# STM32F100_Base_Wireless_2.net
KiCad netlist of a schematic drawn in EAGLE
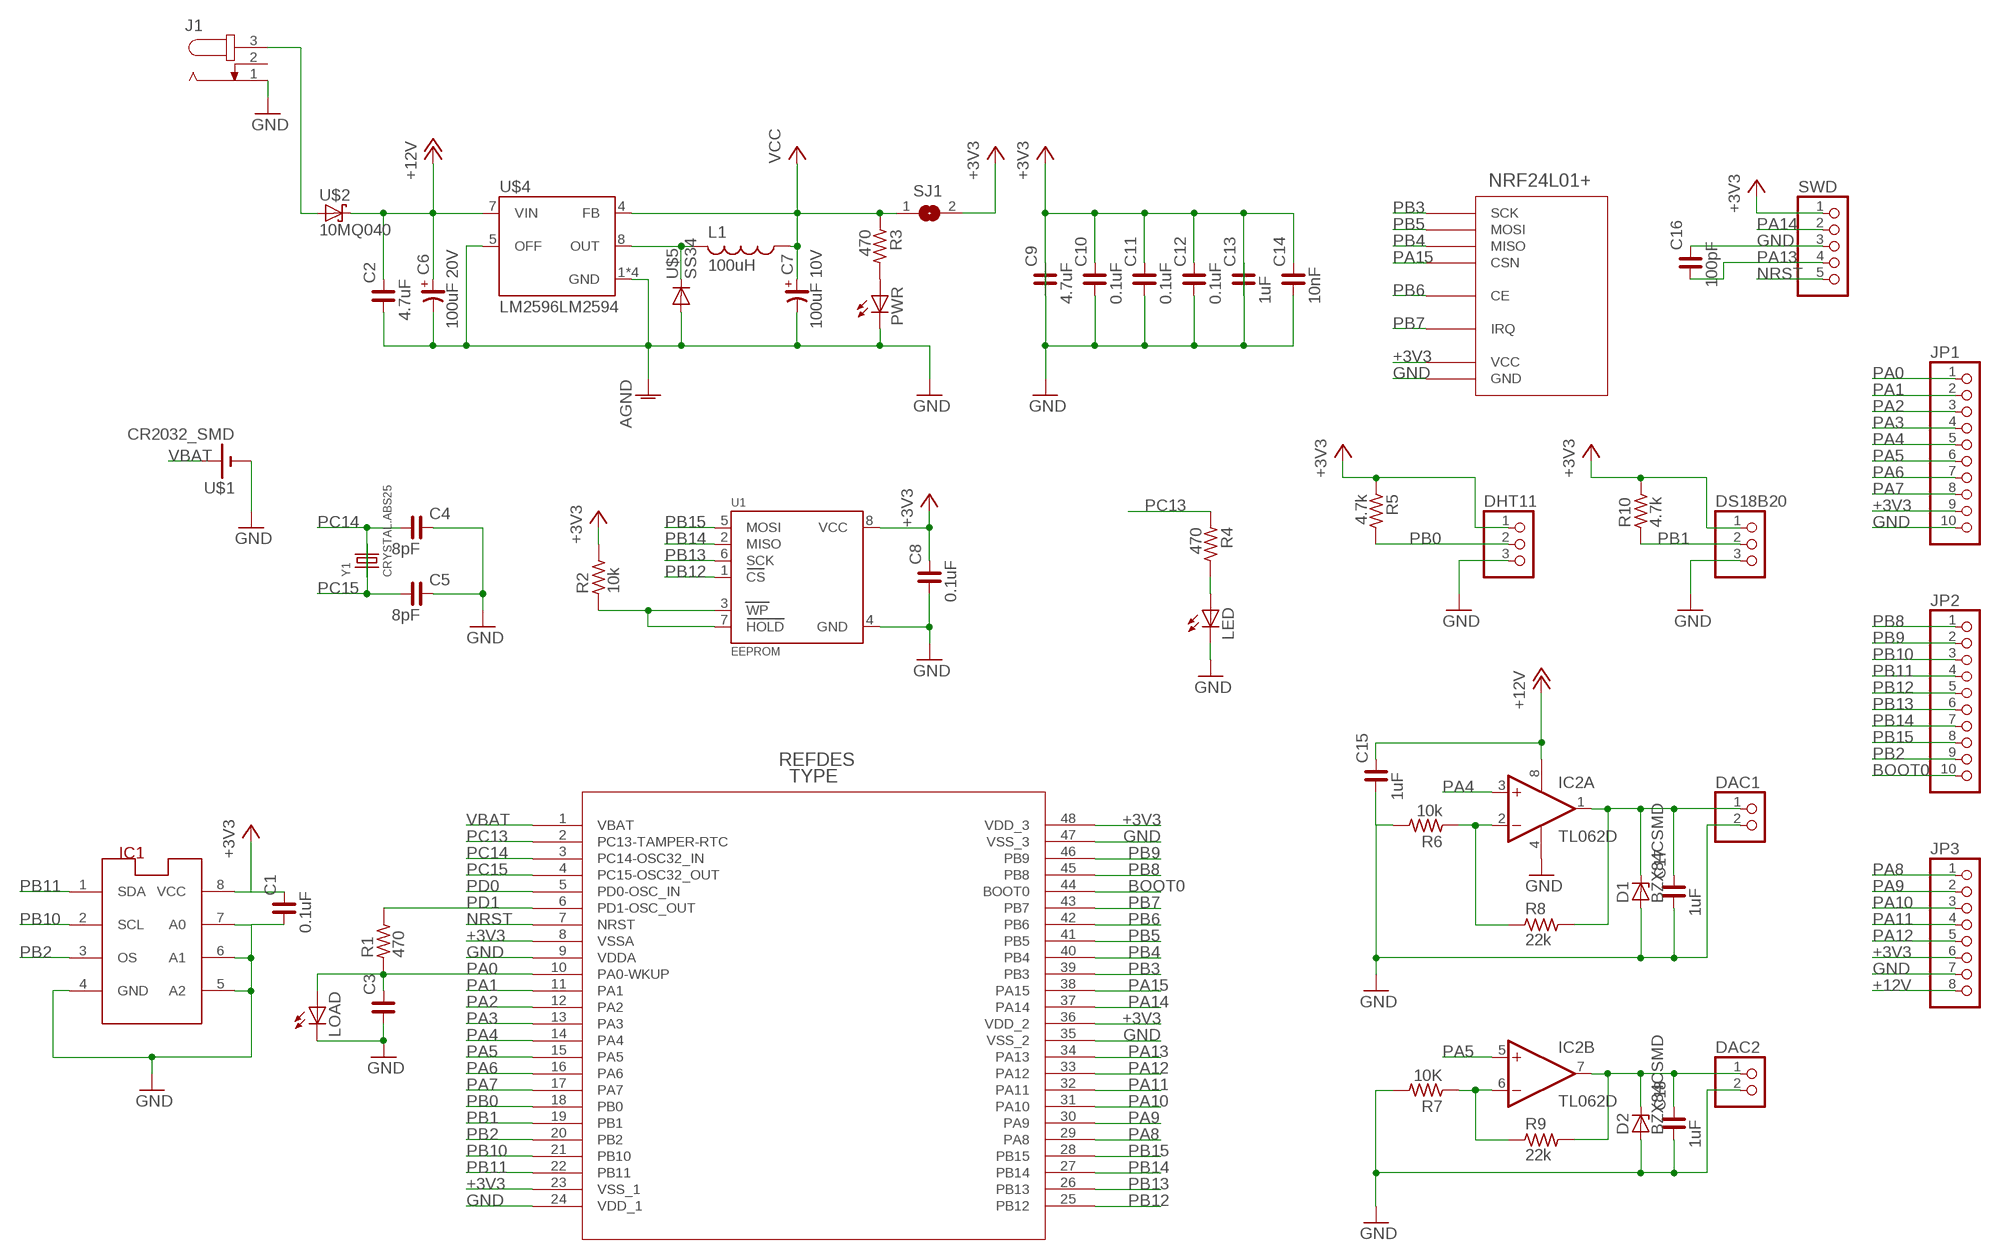
[diagram p0: schematic, sheet 1]

(export (version "E")
  (design (tool "Eeschema 10.0.6"))
  (components
    (comp (ref "C1")
      (value "0.1uF")
      (footprint "eagle-import:C0603")
      (libsource (lib "eagle-import") (part "C_0603"))
    )
    (comp (ref "C2")
      (value "4.7uF")
      (footprint "eagle-import:C0603")
      (libsource (lib "eagle-import") (part "C_0603"))
    )
    (comp (ref "C3")
      (value "C_0603")
      (footprint "eagle-import:C0603")
      (libsource (lib "eagle-import") (part "C_0603"))
    )
    (comp (ref "C4")
      (value "8pF")
      (footprint "eagle-import:C0603")
      (libsource (lib "eagle-import") (part "C_0603"))
    )
    (comp (ref "C5")
      (value "8pF")
      (footprint "eagle-import:C0603")
      (libsource (lib "eagle-import") (part "C_0603"))
    )
    (comp (ref "C6")
      (value "100uF 20V")
      (footprint "eagle-import:C7343_T")
      (libsource (lib "eagle-import") (part "CP_7343"))
    )
    (comp (ref "C7")
      (value "100uF 10V")
      (footprint "eagle-import:C6032-28_T")
      (libsource (lib "eagle-import") (part "CP_6032-28"))
    )
    (comp (ref "C8")
      (value "0.1uF")
      (footprint "eagle-import:C0603")
      (libsource (lib "eagle-import") (part "C_0603"))
    )
    (comp (ref "C9")
      (value "4.7uF")
      (footprint "eagle-import:C0603")
      (libsource (lib "eagle-import") (part "C_0603"))
    )
    (comp (ref "C10")
      (value "0.1uF")
      (footprint "eagle-import:C0603")
      (libsource (lib "eagle-import") (part "C_0603"))
    )
    (comp (ref "C11")
      (value "0.1uF")
      (footprint "eagle-import:C0603")
      (libsource (lib "eagle-import") (part "C_0603"))
    )
    (comp (ref "C12")
      (value "0.1uF")
      (footprint "eagle-import:C0603")
      (libsource (lib "eagle-import") (part "C_0603"))
    )
    (comp (ref "C13")
      (value "1uF")
      (footprint "eagle-import:C0603")
      (libsource (lib "eagle-import") (part "C_0603"))
    )
    (comp (ref "C14")
      (value "10nF")
      (footprint "eagle-import:C0603")
      (libsource (lib "eagle-import") (part "C_0603"))
    )
    (comp (ref "C15")
      (value "1uF")
      (footprint "eagle-import:C0603")
      (libsource (lib "eagle-import") (part "C_0603"))
    )
    (comp (ref "C16")
      (value "100pF")
      (footprint "eagle-import:C0603")
      (libsource (lib "eagle-import") (part "C_0603"))
    )
    (comp (ref "C17")
      (value "1uF")
      (footprint "eagle-import:C0603")
      (libsource (lib "eagle-import") (part "C_0603"))
    )
    (comp (ref "C18")
      (value "1uF")
      (footprint "eagle-import:C0603")
      (libsource (lib "eagle-import") (part "C_0603"))
    )
    (comp (ref "D1")
      (value "BZX84CSMD")
      (footprint "eagle-import:TO236")
      (libsource (lib "eagle-import") (part "BZX84CSMD"))
    )
    (comp (ref "D2")
      (value "BZX84CSMD")
      (footprint "eagle-import:TO236")
      (libsource (lib "eagle-import") (part "BZX84CSMD"))
    )
    (comp (ref "DAC1")
      (value "PINHD-1X02_2.54-S")
      (footprint "eagle-import:1X02-S")
      (libsource (lib "eagle-import") (part "PINHD-1X02_2.54-S"))
    )
    (comp (ref "DAC2")
      (value "PINHD-1X02_2.54-S")
      (footprint "eagle-import:1X02-S")
      (libsource (lib "eagle-import") (part "PINHD-1X02_2.54-S"))
    )
    (comp (ref "DHT11")
      (value "PINHD-1X03_2.54-S")
      (footprint "eagle-import:1X03-S")
      (libsource (lib "eagle-import") (part "PINHD-1X03_2.54-S"))
    )
    (comp (ref "DS18B20")
      (value "PINHD-1X03_2.54-S")
      (footprint "eagle-import:1X03-S")
      (libsource (lib "eagle-import") (part "PINHD-1X03_2.54-S"))
    )
    (comp (ref "IC1")
      (value "LM75_ICN")
      (footprint "eagle-import:SO8_LM75")
      (libsource (lib "eagle-import") (part "LM75_ICN"))
    )
    (comp (ref "IC2")
      (value "TL062D")
      (footprint "eagle-import:SO08")
      (libsource (lib "eagle-import") (part "TL062D"))
    )
    (comp (ref "J1")
      (value "JACK-PLUG0")
      (footprint "eagle-import:SPC4077")
      (libsource (lib "eagle-import") (part "JACK-PLUG0"))
    )
    (comp (ref "JP1")
      (value "PINHD-1X10_2.54-S")
      (footprint "eagle-import:1X10-S")
      (libsource (lib "eagle-import") (part "PINHD-1X10_2.54-S"))
    )
    (comp (ref "JP2")
      (value "PINHD-1X10_2.54-S")
      (footprint "eagle-import:1X10-S")
      (libsource (lib "eagle-import") (part "PINHD-1X10_2.54-S"))
    )
    (comp (ref "JP3")
      (value "PINHD-1X08_2.54-S")
      (footprint "eagle-import:1X08-S")
      (libsource (lib "eagle-import") (part "PINHD-1X08_2.54-S"))
    )
    (comp (ref "L1")
      (value "100uH")
      (footprint "eagle-import:POWER-CHOKE_WE-TPC")
      (libsource (lib "eagle-import") (part "L-USWE-TPC"))
    )
    (comp (ref "LED")
      (value "LEDCHIPLED_1206")
      (footprint "eagle-import:CHIPLED_1206")
      (libsource (lib "eagle-import") (part "LEDCHIPLED_1206"))
    )
    (comp (ref "LOAD")
      (value "LEDCHIPLED_1206")
      (footprint "eagle-import:CHIPLED_1206")
      (libsource (lib "eagle-import") (part "LEDCHIPLED_1206"))
    )
    (comp (ref "PWR")
      (value "LEDCHIPLED_1206")
      (footprint "eagle-import:CHIPLED_1206")
      (libsource (lib "eagle-import") (part "LEDCHIPLED_1206"))
    )
    (comp (ref "R1")
      (value "470")
      (footprint "eagle-import:R1206")
      (libsource (lib "eagle-import") (part "R_1206"))
    )
    (comp (ref "R2")
      (value "10k")
      (footprint "eagle-import:R1206")
      (libsource (lib "eagle-import") (part "R_1206"))
    )
    (comp (ref "R3")
      (value "470")
      (footprint "eagle-import:R1206")
      (libsource (lib "eagle-import") (part "R_1206"))
    )
    (comp (ref "R4")
      (value "470")
      (footprint "eagle-import:R1206")
      (libsource (lib "eagle-import") (part "R_1206"))
    )
    (comp (ref "R5")
      (value "4.7k")
      (footprint "eagle-import:R1206")
      (libsource (lib "eagle-import") (part "R_1206"))
    )
    (comp (ref "R6")
      (value "10k")
      (footprint "eagle-import:R1206")
      (libsource (lib "eagle-import") (part "R_1206"))
    )
    (comp (ref "R7")
      (value "10K")
      (footprint "eagle-import:R1206")
      (libsource (lib "eagle-import") (part "R_1206"))
    )
    (comp (ref "R8")
      (value "22k")
      (footprint "eagle-import:R1206")
      (libsource (lib "eagle-import") (part "R_1206"))
    )
    (comp (ref "R9")
      (value "22k")
      (footprint "eagle-import:R1206")
      (libsource (lib "eagle-import") (part "R_1206"))
    )
    (comp (ref "R10")
      (value "4.7k")
      (footprint "eagle-import:R1206")
      (libsource (lib "eagle-import") (part "R_1206"))
    )
    (comp (ref "SJ1") (value "SJ") (footprint "eagle-import:SJ") (libsource (lib "eagle-import") (part "SJ")))
    (comp (ref "SWD")
      (value "PINHD-1X05_2.54-90°-S")
      (footprint "eagle-import:1X05_90-S")
      (libsource (lib "eagle-import") (part "PINHD-1X05_2.54-90°-S"))
    )
    (comp (ref "U$1")
      (value "CR2032_SMD")
      (footprint "eagle-import:SMD_BH-2")
      (libsource (lib "eagle-import") (part "CR2032_SMD"))
    )
    (comp (ref "U$2")
      (value "10MQ040")
      (footprint "eagle-import:SMA")
      (libsource (lib "eagle-import") (part "10MQ040"))
    )
    (comp (ref "U$3")
      (value "STM32F100C8T6B")
      (footprint "eagle-import:LQFP-48")
      (libsource (lib "eagle-import") (part "STM32F100C8T6B"))
    )
    (comp (ref "U$4")
      (value "LM2596LM2594")
      (footprint "eagle-import:SOIC8_150MIL")
      (libsource (lib "eagle-import") (part "LM2596LM2594"))
    )
    (comp (ref "U$5")
      (value "SS34")
      (footprint "eagle-import:DO214AC")
      (libsource (lib "eagle-import") (part "DIODE-DO214AC"))
    )
    (comp (ref "U$6")
      (value "NRF24L01+")
      (footprint "eagle-import:NRF24L01+")
      (libsource (lib "eagle-import") (part "NRF24L01+"))
    )
    (comp (ref "U1")
      (value "EEPROM")
      (footprint "eagle-import:SOIC8_150MIL")
      (libsource (lib "eagle-import") (part "EEPROM_SPI_AT25040A"))
    )
    (comp (ref "Y1")
      (value "CRYSTAL.ABS25")
      (footprint "eagle-import:ABS25")
      (libsource (lib "eagle-import") (part "CRYSTAL.ABS25"))
    )
  )
  (nets
    (net (code "1") (name "+3V3") (class "Default")
      (node (ref "C1") (pin "2") (pinfunction "2_2") (pintype "passive"))
      (node (ref "C10") (pin "2") (pinfunction "2_2") (pintype "passive"))
      (node (ref "C11") (pin "2") (pinfunction "2_2") (pintype "passive"))
      (node (ref "C12") (pin "2") (pinfunction "2_2") (pintype "passive"))
      (node (ref "C13") (pin "1") (pinfunction "1_1") (pintype "passive"))
      (node (ref "C14") (pin "2") (pinfunction "2_2") (pintype "passive"))
      (node (ref "C8") (pin "2") (pinfunction "2_2") (pintype "passive"))
      (node (ref "C9") (pin "1") (pinfunction "1_1") (pintype "passive"))
      (node (ref "DHT11") (pin "1") (pinfunction "1_1") (pintype "passive"))
      (node (ref "DS18B20") (pin "1") (pinfunction "1_1") (pintype "passive"))
      (node (ref "IC1") (pin "8") (pinfunction "VCC_8") (pintype "power_in"))
      (node (ref "JP1") (pin "9") (pinfunction "9_9") (pintype "passive"))
      (node (ref "JP3") (pin "6") (pinfunction "6_6") (pintype "passive"))
      (node (ref "R10") (pin "2") (pinfunction "2_2") (pintype "passive"))
      (node (ref "R2") (pin "2") (pinfunction "2_2") (pintype "passive"))
      (node (ref "R5") (pin "1") (pinfunction "1_1") (pintype "passive"))
      (node (ref "SJ1") (pin "2") (pinfunction "2_2") (pintype "passive"))
      (node (ref "SWD") (pin "1") (pinfunction "1_1") (pintype "passive"))
      (node (ref "U$3") (pin "23") (pinfunction "VSS_1_23") (pintype "passive"))
      (node (ref "U$3") (pin "36") (pinfunction "VDD_2_36") (pintype "passive"))
      (node (ref "U$3") (pin "48") (pinfunction "VDD_3_48") (pintype "passive"))
      (node (ref "U$3") (pin "8") (pinfunction "VSSA_8") (pintype "passive"))
      (node (ref "U$6") (pin "VCC") (pinfunction "VCC_VCC") (pintype "passive"))
      (node (ref "U1") (pin "8") (pinfunction "VCC_8") (pintype "power_in"))
    )
    (net (code "2") (name "+12V") (class "Default")
      (node (ref "C15") (pin "2") (pinfunction "2_2") (pintype "passive"))
      (node (ref "C2") (pin "2") (pinfunction "2_2") (pintype "passive"))
      (node (ref "C6") (pin "+") (pinfunction "+_+") (pintype "passive"))
      (node (ref "IC2") (pin "8") (pinfunction "V+_8") (pintype "power_in"))
      (node (ref "JP3") (pin "8") (pinfunction "8_8") (pintype "passive"))
      (node (ref "U$2") (pin "C") (pinfunction "C_C") (pintype "passive"))
      (node (ref "U$4") (pin "7") (pinfunction "VIN_7") (pintype "power_in"))
    )
    (net (code "3") (name "/BOOT0") (class "Default")
      (node (ref "JP2") (pin "10") (pinfunction "10_10") (pintype "passive"))
      (node (ref "U$3") (pin "44") (pinfunction "BOOT0_44") (pintype "passive"))
    )
    (net (code "4") (name "/NRST") (class "Default")
      (node (ref "SWD") (pin "5") (pinfunction "5_5") (pintype "passive"))
      (node (ref "U$3") (pin "7") (pinfunction "NRST_7") (pintype "passive"))
    )
    (net (code "5") (name "/PA0") (class "Default")
      (node (ref "C3") (pin "2") (pinfunction "2_2") (pintype "passive"))
      (node (ref "JP1") (pin "1") (pinfunction "1_1") (pintype "passive"))
      (node (ref "LOAD") (pin "A") (pinfunction "A_A") (pintype "passive"))
      (node (ref "R1") (pin "1") (pinfunction "1_1") (pintype "passive"))
      (node (ref "U$3") (pin "10") (pinfunction "PA0-WKUP_10") (pintype "passive"))
    )
    (net (code "6") (name "/PA1") (class "Default")
      (node (ref "JP1") (pin "2") (pinfunction "2_2") (pintype "passive"))
      (node (ref "U$3") (pin "11") (pinfunction "PA1_11") (pintype "passive"))
    )
    (net (code "7") (name "/PA2") (class "Default")
      (node (ref "JP1") (pin "3") (pinfunction "3_3") (pintype "passive"))
      (node (ref "U$3") (pin "12") (pinfunction "PA2_12") (pintype "passive"))
    )
    (net (code "8") (name "/PA3") (class "Default")
      (node (ref "JP1") (pin "4") (pinfunction "4_4") (pintype "passive"))
      (node (ref "U$3") (pin "13") (pinfunction "PA3_13") (pintype "passive"))
    )
    (net (code "9") (name "/PA4") (class "Default")
      (node (ref "IC2") (pin "3") (pinfunction "+IN_3") (pintype "input"))
      (node (ref "JP1") (pin "5") (pinfunction "5_5") (pintype "passive"))
      (node (ref "U$3") (pin "14") (pinfunction "PA4_14") (pintype "passive"))
    )
    (net (code "10") (name "/PA5") (class "Default")
      (node (ref "IC2") (pin "5") (pinfunction "+IN_5") (pintype "input"))
      (node (ref "JP1") (pin "6") (pinfunction "6_6") (pintype "passive"))
      (node (ref "U$3") (pin "15") (pinfunction "PA5_15") (pintype "passive"))
    )
    (net (code "11") (name "/PA6") (class "Default")
      (node (ref "JP1") (pin "7") (pinfunction "7_7") (pintype "passive"))
      (node (ref "U$3") (pin "16") (pinfunction "PA6_16") (pintype "passive"))
    )
    (net (code "12") (name "/PA7") (class "Default")
      (node (ref "JP1") (pin "8") (pinfunction "8_8") (pintype "passive"))
      (node (ref "U$3") (pin "17") (pinfunction "PA7_17") (pintype "passive"))
    )
    (net (code "13") (name "/PA8") (class "Default")
      (node (ref "JP3") (pin "1") (pinfunction "1_1") (pintype "passive"))
      (node (ref "U$3") (pin "29") (pinfunction "PA8_29") (pintype "passive"))
    )
    (net (code "14") (name "/PA9") (class "Default")
      (node (ref "JP3") (pin "2") (pinfunction "2_2") (pintype "passive"))
      (node (ref "U$3") (pin "30") (pinfunction "PA9_30") (pintype "passive"))
    )
    (net (code "15") (name "/PA10") (class "Default")
      (node (ref "JP3") (pin "3") (pinfunction "3_3") (pintype "passive"))
      (node (ref "U$3") (pin "31") (pinfunction "PA10_31") (pintype "passive"))
    )
    (net (code "16") (name "/PA11") (class "Default")
      (node (ref "JP3") (pin "4") (pinfunction "4_4") (pintype "passive"))
      (node (ref "U$3") (pin "32") (pinfunction "PA11_32") (pintype "passive"))
    )
    (net (code "17") (name "/PA12") (class "Default")
      (node (ref "JP3") (pin "5") (pinfunction "5_5") (pintype "passive"))
      (node (ref "U$3") (pin "33") (pinfunction "PA12_33") (pintype "passive"))
    )
    (net (code "18") (name "/PA13") (class "Default")
      (node (ref "C16") (pin "1") (pinfunction "1_1") (pintype "passive"))
      (node (ref "SWD") (pin "4") (pinfunction "4_4") (pintype "passive"))
      (node (ref "U$3") (pin "34") (pinfunction "PA13_34") (pintype "passive"))
    )
    (net (code "19") (name "/PA14") (class "Default")
      (node (ref "SWD") (pin "2") (pinfunction "2_2") (pintype "passive"))
      (node (ref "U$3") (pin "37") (pinfunction "PA14_37") (pintype "passive"))
    )
    (net (code "20") (name "/PA15") (class "Default")
      (node (ref "U$3") (pin "38") (pinfunction "PA15_38") (pintype "passive"))
      (node (ref "U$6") (pin "CSN") (pinfunction "CSN_CSN") (pintype "passive"))
    )
    (net (code "21") (name "/PB0") (class "Default")
      (node (ref "DHT11") (pin "2") (pinfunction "2_2") (pintype "passive"))
      (node (ref "R5") (pin "2") (pinfunction "2_2") (pintype "passive"))
      (node (ref "U$3") (pin "18") (pinfunction "PB0_18") (pintype "passive"))
    )
    (net (code "22") (name "/PB1") (class "Default")
      (node (ref "DS18B20") (pin "2") (pinfunction "2_2") (pintype "passive"))
      (node (ref "R10") (pin "1") (pinfunction "1_1") (pintype "passive"))
      (node (ref "U$3") (pin "19") (pinfunction "PB1_19") (pintype "passive"))
    )
    (net (code "23") (name "/PB2") (class "Default")
      (node (ref "IC1") (pin "3") (pinfunction "OS_3") (pintype "output"))
      (node (ref "JP2") (pin "9") (pinfunction "9_9") (pintype "passive"))
      (node (ref "U$3") (pin "20") (pinfunction "PB2_20") (pintype "passive"))
    )
    (net (code "24") (name "/PB3") (class "Default")
      (node (ref "U$3") (pin "39") (pinfunction "PB3_39") (pintype "passive"))
      (node (ref "U$6") (pin "SCK") (pinfunction "SCK_SCK") (pintype "passive"))
    )
    (net (code "25") (name "/PB4") (class "Default")
      (node (ref "U$3") (pin "40") (pinfunction "PB4_40") (pintype "passive"))
      (node (ref "U$6") (pin "MISO") (pinfunction "MISO_MISO") (pintype "passive"))
    )
    (net (code "26") (name "/PB5") (class "Default")
      (node (ref "U$3") (pin "41") (pinfunction "PB5_41") (pintype "passive"))
      (node (ref "U$6") (pin "MOSI") (pinfunction "MOSI_MOSI") (pintype "passive"))
    )
    (net (code "27") (name "/PB6") (class "Default")
      (node (ref "U$3") (pin "42") (pinfunction "PB6_42") (pintype "passive"))
      (node (ref "U$6") (pin "CE") (pinfunction "CE_CE") (pintype "passive"))
    )
    (net (code "28") (name "/PB7") (class "Default")
      (node (ref "U$3") (pin "43") (pinfunction "PB7_43") (pintype "passive"))
      (node (ref "U$6") (pin "IRQ") (pinfunction "IRQ_IRQ") (pintype "passive"))
    )
    (net (code "29") (name "/PB8") (class "Default")
      (node (ref "JP2") (pin "1") (pinfunction "1_1") (pintype "passive"))
      (node (ref "U$3") (pin "45") (pinfunction "PB8_45") (pintype "passive"))
    )
    (net (code "30") (name "/PB9") (class "Default")
      (node (ref "JP2") (pin "2") (pinfunction "2_2") (pintype "passive"))
      (node (ref "U$3") (pin "46") (pinfunction "PB9_46") (pintype "passive"))
    )
    (net (code "31") (name "/PB10") (class "Default")
      (node (ref "IC1") (pin "2") (pinfunction "SCL_2") (pintype "bidirectional"))
      (node (ref "JP2") (pin "3") (pinfunction "3_3") (pintype "passive"))
      (node (ref "U$3") (pin "21") (pinfunction "PB10_21") (pintype "passive"))
    )
    (net (code "32") (name "/PB11") (class "Default")
      (node (ref "IC1") (pin "1") (pinfunction "SDA_1") (pintype "bidirectional"))
      (node (ref "JP2") (pin "4") (pinfunction "4_4") (pintype "passive"))
      (node (ref "U$3") (pin "22") (pinfunction "PB11_22") (pintype "passive"))
    )
    (net (code "33") (name "/PB12") (class "Default")
      (node (ref "JP2") (pin "5") (pinfunction "5_5") (pintype "passive"))
      (node (ref "U$3") (pin "25") (pinfunction "PB12_25") (pintype "passive"))
      (node (ref "U1") (pin "1") (pinfunction "CS_1") (pintype "bidirectional"))
    )
    (net (code "34") (name "/PB13") (class "Default")
      (node (ref "JP2") (pin "6") (pinfunction "6_6") (pintype "passive"))
      (node (ref "U$3") (pin "26") (pinfunction "PB13_26") (pintype "passive"))
      (node (ref "U1") (pin "6") (pinfunction "SCK_6") (pintype "bidirectional"))
    )
    (net (code "35") (name "/PB14") (class "Default")
      (node (ref "JP2") (pin "7") (pinfunction "7_7") (pintype "passive"))
      (node (ref "U$3") (pin "27") (pinfunction "PB14_27") (pintype "passive"))
      (node (ref "U1") (pin "2") (pinfunction "MISO_2") (pintype "bidirectional"))
    )
    (net (code "36") (name "/PB15") (class "Default")
      (node (ref "JP2") (pin "8") (pinfunction "8_8") (pintype "passive"))
      (node (ref "U$3") (pin "28") (pinfunction "PB15_28") (pintype "passive"))
      (node (ref "U1") (pin "5") (pinfunction "MOSI_5") (pintype "bidirectional"))
    )
    (net (code "37") (name "/PC13") (class "Default")
      (node (ref "R4") (pin "1") (pinfunction "1_1") (pintype "passive"))
      (node (ref "U$3") (pin "2") (pinfunction "PC13-TAMPER-RTC_2") (pintype "passive"))
    )
    (net (code "38") (name "/PC14") (class "Default")
      (node (ref "C4") (pin "1") (pinfunction "1_1") (pintype "passive"))
      (node (ref "U$3") (pin "3") (pinfunction "PC14-OSC32_IN_3") (pintype "passive"))
      (node (ref "Y1") (pin "1") (pinfunction "1_1") (pintype "passive"))
    )
    (net (code "39") (name "/PC15") (class "Default")
      (node (ref "C5") (pin "1") (pinfunction "1_1") (pintype "passive"))
      (node (ref "U$3") (pin "4") (pinfunction "PC15-OSC32_OUT_4") (pintype "passive"))
      (node (ref "Y1") (pin "4") (pinfunction "2_4") (pintype "passive"))
    )
    (net (code "40") (name "/PD0") (class "Default")
      (node (ref "U$3") (pin "5") (pinfunction "PD0-OSC_IN_5") (pintype "passive"))
    )
    (net (code "41") (name "/PD1") (class "Default")
      (node (ref "R1") (pin "2") (pinfunction "2_2") (pintype "passive"))
      (node (ref "U$3") (pin "6") (pinfunction "PD1-OSC_OUT_6") (pintype "passive"))
    )
    (net (code "42") (name "/VBAT") (class "Default")
      (node (ref "U$1") (pin "P$POS1") (pinfunction "+_P$POS1") (pintype "passive"))
      (node (ref "U$3") (pin "1") (pinfunction "VBAT_1") (pintype "passive"))
    )
    (net (code "43") (name "AGND") (class "Default")
      (node (ref "C1") (pin "1") (pinfunction "1_1") (pintype "passive"))
      (node (ref "C10") (pin "1") (pinfunction "1_1") (pintype "passive"))
      (node (ref "C11") (pin "1") (pinfunction "1_1") (pintype "passive"))
      (node (ref "C12") (pin "1") (pinfunction "1_1") (pintype "passive"))
      (node (ref "C13") (pin "2") (pinfunction "2_2") (pintype "passive"))
      (node (ref "C14") (pin "1") (pinfunction "1_1") (pintype "passive"))
      (node (ref "C15") (pin "1") (pinfunction "1_1") (pintype "passive"))
      (node (ref "C16") (pin "2") (pinfunction "2_2") (pintype "passive"))
      (node (ref "C17") (pin "1") (pinfunction "1_1") (pintype "passive"))
      (node (ref "C18") (pin "1") (pinfunction "1_1") (pintype "passive"))
      (node (ref "C2") (pin "1") (pinfunction "1_1") (pintype "passive"))
      (node (ref "C3") (pin "1") (pinfunction "1_1") (pintype "passive"))
      (node (ref "C4") (pin "2") (pinfunction "2_2") (pintype "passive"))
      (node (ref "C5") (pin "2") (pinfunction "2_2") (pintype "passive"))
      (node (ref "C6") (pin "-") (pinfunction "-_-") (pintype "passive"))
      (node (ref "C7") (pin "-") (pinfunction "-_-") (pintype "passive"))
      (node (ref "C8") (pin "1") (pinfunction "1_1") (pintype "passive"))
      (node (ref "C9") (pin "2") (pinfunction "2_2") (pintype "passive"))
      (node (ref "D1") (pin "A") (pinfunction "A_A") (pintype "passive"))
      (node (ref "D2") (pin "A") (pinfunction "A_A") (pintype "passive"))
      (node (ref "DAC1") (pin "2") (pinfunction "2_2") (pintype "passive"))
      (node (ref "DAC2") (pin "2") (pinfunction "2_2") (pintype "passive"))
      (node (ref "DHT11") (pin "3") (pinfunction "3_3") (pintype "passive"))
      (node (ref "DS18B20") (pin "3") (pinfunction "3_3") (pintype "passive"))
      (node (ref "IC1") (pin "4") (pinfunction "GND_4") (pintype "power_in"))
      (node (ref "IC1") (pin "5") (pinfunction "A2_5") (pintype "input"))
      (node (ref "IC1") (pin "6") (pinfunction "A1_6") (pintype "input"))
      (node (ref "IC1") (pin "7") (pinfunction "A0_7") (pintype "input"))
      (node (ref "IC2") (pin "4") (pinfunction "V-_4") (pintype "power_in"))
      (node (ref "J1") (pin "1") (pinfunction "1_1") (pintype "passive"))
      (node (ref "JP1") (pin "10") (pinfunction "10_10") (pintype "passive"))
      (node (ref "JP3") (pin "7") (pinfunction "7_7") (pintype "passive"))
      (node (ref "LED") (pin "C") (pinfunction "C_C") (pintype "passive"))
      (node (ref "LOAD") (pin "C") (pinfunction "C_C") (pintype "passive"))
      (node (ref "PWR") (pin "C") (pinfunction "C_C") (pintype "passive"))
      (node (ref "R6") (pin "2") (pinfunction "2_2") (pintype "passive"))
      (node (ref "R7") (pin "2") (pinfunction "2_2") (pintype "passive"))
      (node (ref "SWD") (pin "3") (pinfunction "3_3") (pintype "passive"))
      (node (ref "U$1") (pin "P$NEG") (pinfunction "-_P$NEG") (pintype "passive"))
      (node (ref "U$3") (pin "24") (pinfunction "VDD_1_24") (pintype "passive"))
      (node (ref "U$3") (pin "35") (pinfunction "VSS_2_35") (pintype "passive"))
      (node (ref "U$3") (pin "47") (pinfunction "VSS_3_47") (pintype "passive"))
      (node (ref "U$3") (pin "9") (pinfunction "VDDA_9") (pintype "passive"))
      (node (ref "U$4") (pin "1") (pinfunction "GND_1") (pintype "power_in"))
      (node (ref "U$4") (pin "2") (pinfunction "GND_2") (pintype "power_in"))
      (node (ref "U$4") (pin "3") (pinfunction "GND_3") (pintype "power_in"))
      (node (ref "U$4") (pin "5") (pinfunction "OFF_5") (pintype "input"))
      (node (ref "U$4") (pin "6") (pinfunction "GND_6") (pintype "power_in"))
      (node (ref "U$5") (pin "A") (pinfunction "A_A") (pintype "passive"))
      (node (ref "U$6") (pin "GND") (pinfunction "GND_GND") (pintype "passive"))
      (node (ref "U1") (pin "4") (pinfunction "GND_4") (pintype "power_in"))
    )
    (net (code "44") (name "Net-(IC2A--IN)") (class "Default")
      (node (ref "IC2") (pin "2") (pinfunction "-IN_2") (pintype "input"))
      (node (ref "R6") (pin "1") (pinfunction "1_1") (pintype "passive"))
      (node (ref "R8") (pin "1") (pinfunction "1_1") (pintype "passive"))
    )
    (net (code "45") (name "Net-(IC2A-OUT)") (class "Default")
      (node (ref "C17") (pin "2") (pinfunction "2_2") (pintype "passive"))
      (node (ref "D1") (pin "C") (pinfunction "C_C") (pintype "passive"))
      (node (ref "DAC1") (pin "1") (pinfunction "1_1") (pintype "passive"))
      (node (ref "IC2") (pin "1") (pinfunction "OUT_1") (pintype "output"))
      (node (ref "R8") (pin "2") (pinfunction "2_2") (pintype "passive"))
    )
    (net (code "46") (name "Net-(IC2B--IN)") (class "Default")
      (node (ref "IC2") (pin "6") (pinfunction "-IN_6") (pintype "input"))
      (node (ref "R7") (pin "1") (pinfunction "1_1") (pintype "passive"))
      (node (ref "R9") (pin "1") (pinfunction "1_1") (pintype "passive"))
    )
    (net (code "47") (name "Net-(IC2B-OUT)") (class "Default")
      (node (ref "C18") (pin "2") (pinfunction "2_2") (pintype "passive"))
      (node (ref "D2") (pin "C") (pinfunction "C_C") (pintype "passive"))
      (node (ref "DAC2") (pin "1") (pinfunction "1_1") (pintype "passive"))
      (node (ref "IC2") (pin "7") (pinfunction "OUT_7") (pintype "output"))
      (node (ref "R9") (pin "2") (pinfunction "2_2") (pintype "passive"))
    )
    (net (code "48") (name "Net-(J1-Pad3)") (class "Default")
      (node (ref "J1") (pin "3") (pinfunction "3_3") (pintype "passive"))
      (node (ref "U$2") (pin "A") (pinfunction "A_A") (pintype "passive"))
    )
    (net (code "49") (name "Net-(LED-PadA)") (class "Default")
      (node (ref "LED") (pin "A") (pinfunction "A_A") (pintype "passive"))
      (node (ref "R4") (pin "2") (pinfunction "2_2") (pintype "passive"))
    )
    (net (code "50") (name "Net-(PWR-PadA)") (class "Default")
      (node (ref "PWR") (pin "A") (pinfunction "A_A") (pintype "passive"))
      (node (ref "R3") (pin "2") (pinfunction "2_2") (pintype "passive"))
    )
    (net (code "51") (name "Net-(U$4-OUT)") (class "Default")
      (node (ref "L1") (pin "2") (pinfunction "2_2") (pintype "passive"))
      (node (ref "U$4") (pin "8") (pinfunction "OUT_8") (pintype "output"))
      (node (ref "U$5") (pin "C") (pinfunction "C_C") (pintype "passive"))
    )
    (net (code "52") (name "Net-(U1-HOLD)") (class "Default")
      (node (ref "R2") (pin "1") (pinfunction "1_1") (pintype "passive"))
      (node (ref "U1") (pin "3") (pinfunction "WP_3") (pintype "bidirectional"))
      (node (ref "U1") (pin "7") (pinfunction "HOLD_7") (pintype "bidirectional"))
    )
    (net (code "53") (name "VCC") (class "Default")
      (node (ref "C7") (pin "+") (pinfunction "+_+") (pintype "passive"))
      (node (ref "L1") (pin "1") (pinfunction "1_1") (pintype "passive"))
      (node (ref "R3") (pin "1") (pinfunction "1_1") (pintype "passive"))
      (node (ref "SJ1") (pin "1") (pinfunction "1_1") (pintype "passive"))
      (node (ref "U$4") (pin "4") (pinfunction "FB_4") (pintype "input"))
    )
    (net (code "54") (name "unconnected-(J1-Pad2)") (class "Default")
      (node (ref "J1") (pin "2") (pinfunction "2_2") (pintype "passive"))
    )
  )
)
